# Ventilation.net
KiCad netlist of a schematic drawn in EAGLE
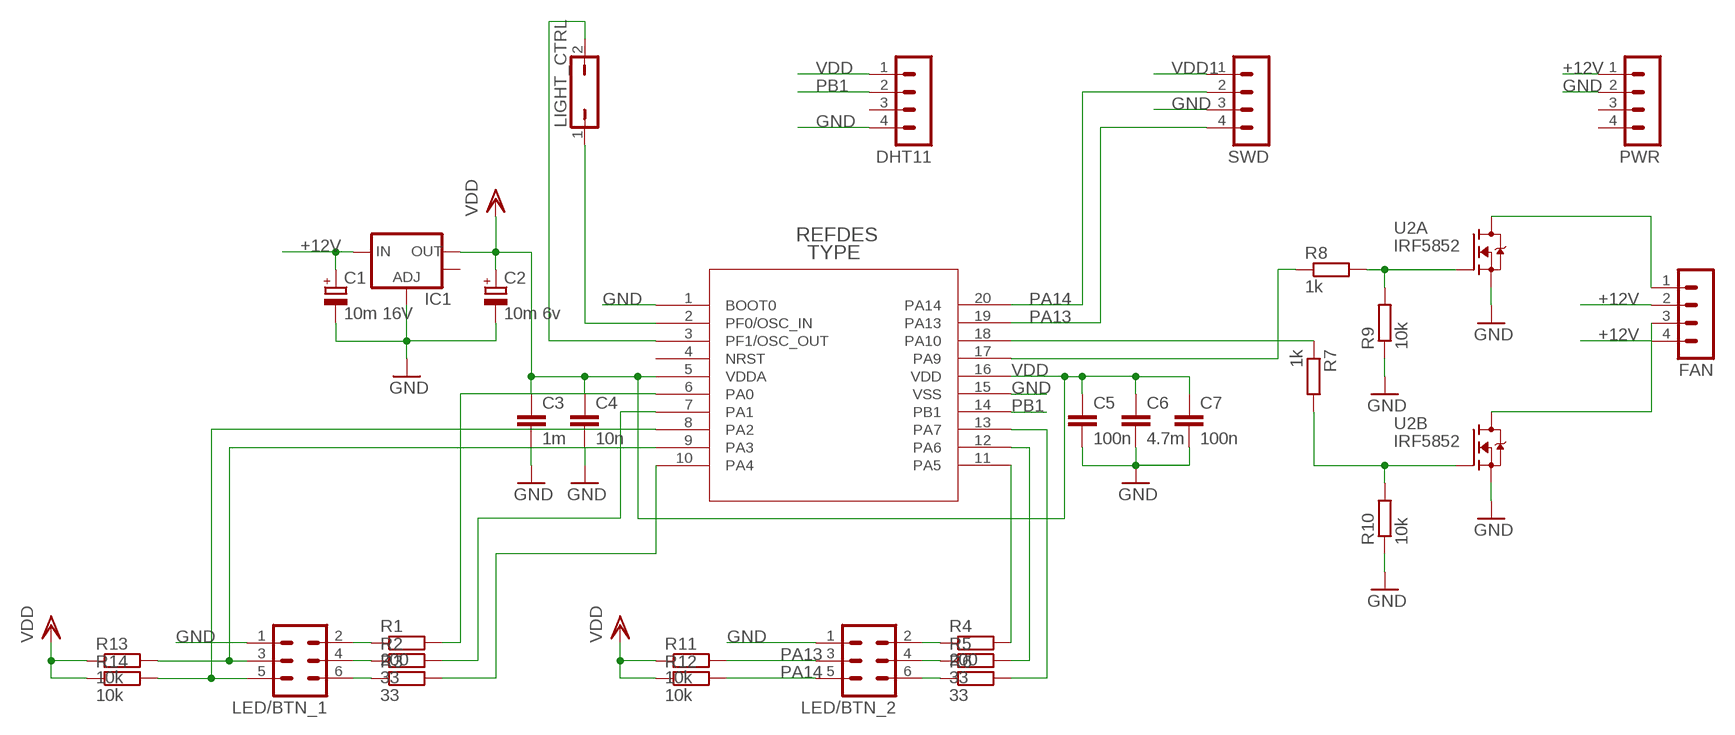
[diagram p0: schematic, sheet 1]

(export (version "E")
  (design (tool "Eeschema 10.0.6"))
  (components
    (comp (ref "C1")
      (value "10m 16V")
      (footprint "eagle-import:SMC_A")
      (libsource (lib "eagle-import") (part "CPOL-EUSMCA"))
    )
    (comp (ref "C2")
      (value "10m 6v")
      (footprint "eagle-import:SMC_A")
      (libsource (lib "eagle-import") (part "CPOL-EUSMCA"))
    )
    (comp (ref "C3")
      (value "1m")
      (footprint "eagle-import:C1206")
      (libsource (lib "eagle-import") (part "C-EUC1206"))
    )
    (comp (ref "C4")
      (value "10n")
      (footprint "eagle-import:C1206")
      (libsource (lib "eagle-import") (part "C-EUC1206"))
    )
    (comp (ref "C5")
      (value "100n")
      (footprint "eagle-import:C1206")
      (libsource (lib "eagle-import") (part "C-EUC1206"))
    )
    (comp (ref "C6")
      (value "4.7m")
      (footprint "eagle-import:C1206")
      (libsource (lib "eagle-import") (part "C-EUC1206"))
    )
    (comp (ref "C7")
      (value "100n")
      (footprint "eagle-import:C1206")
      (libsource (lib "eagle-import") (part "C-EUC1206"))
    )
    (comp (ref "DHT11")
      (value "MA04-1")
      (footprint "eagle-import:MA04-1")
      (libsource (lib "eagle-import") (part "MA04-1"))
    )
    (comp (ref "FAN")
      (value "MA04-1")
      (footprint "eagle-import:MA04-1")
      (libsource (lib "eagle-import") (part "MA04-1"))
    )
    (comp (ref "IC1")
      (value "V_REG_LM1117SOT223")
      (footprint "eagle-import:SOT223")
      (libsource (lib "eagle-import") (part "V_REG_LM1117SOT223"))
    )
    (comp (ref "LED/BTN_1")
      (value "MA03-2")
      (footprint "eagle-import:MA03-2")
      (libsource (lib "eagle-import") (part "MA03-2"))
    )
    (comp (ref "LED/BTN_2")
      (value "MA03-2")
      (footprint "eagle-import:MA03-2")
      (libsource (lib "eagle-import") (part "MA03-2"))
    )
    (comp (ref "LIGHT_CTRL")
      (value "JP1Q")
      (footprint "eagle-import:JP1")
      (libsource (lib "eagle-import") (part "JP1Q"))
    )
    (comp (ref "PWR")
      (value "MA04-1")
      (footprint "eagle-import:MA04-1")
      (libsource (lib "eagle-import") (part "MA04-1"))
    )
    (comp (ref "R1")
      (value "200")
      (footprint "eagle-import:R1206")
      (libsource (lib "eagle-import") (part "R-EU_R1206"))
    )
    (comp (ref "R2")
      (value "33")
      (footprint "eagle-import:R1206")
      (libsource (lib "eagle-import") (part "R-EU_R1206"))
    )
    (comp (ref "R3")
      (value "33")
      (footprint "eagle-import:R1206")
      (libsource (lib "eagle-import") (part "R-EU_R1206"))
    )
    (comp (ref "R4")
      (value "200")
      (footprint "eagle-import:R1206")
      (libsource (lib "eagle-import") (part "R-EU_R1206"))
    )
    (comp (ref "R5")
      (value "33")
      (footprint "eagle-import:R1206")
      (libsource (lib "eagle-import") (part "R-EU_R1206"))
    )
    (comp (ref "R6")
      (value "33")
      (footprint "eagle-import:R1206")
      (libsource (lib "eagle-import") (part "R-EU_R1206"))
    )
    (comp (ref "R7")
      (value "1k")
      (footprint "eagle-import:R1206")
      (libsource (lib "eagle-import") (part "R-EU_R1206"))
    )
    (comp (ref "R8")
      (value "1k")
      (footprint "eagle-import:R1206")
      (libsource (lib "eagle-import") (part "R-EU_R1206"))
    )
    (comp (ref "R9")
      (value "10k")
      (footprint "eagle-import:R1206")
      (libsource (lib "eagle-import") (part "R-EU_R1206"))
    )
    (comp (ref "R10")
      (value "10k")
      (footprint "eagle-import:R1206")
      (libsource (lib "eagle-import") (part "R-EU_R1206"))
    )
    (comp (ref "R11")
      (value "10k")
      (footprint "eagle-import:R1206")
      (libsource (lib "eagle-import") (part "R-EU_R1206"))
    )
    (comp (ref "R12")
      (value "10k")
      (footprint "eagle-import:R1206")
      (libsource (lib "eagle-import") (part "R-EU_R1206"))
    )
    (comp (ref "R13")
      (value "10k")
      (footprint "eagle-import:R1206")
      (libsource (lib "eagle-import") (part "R-EU_R1206"))
    )
    (comp (ref "R14")
      (value "10k")
      (footprint "eagle-import:R1206")
      (libsource (lib "eagle-import") (part "R-EU_R1206"))
    )
    (comp (ref "SWD")
      (value "MA04-1")
      (footprint "eagle-import:MA04-1")
      (libsource (lib "eagle-import") (part "MA04-1"))
    )
    (comp (ref "U$1")
      (value "STM32F050F4P6")
      (footprint "eagle-import:TSSOP20")
      (libsource (lib "eagle-import") (part "STM32F050F4P6"))
    )
    (comp (ref "U2")
      (value "IRF5852")
      (footprint "eagle-import:SOT23-6")
      (libsource (lib "eagle-import") (part "IRF5852"))
    )
  )
  (nets
    (net (code "1") (name "/+12V") (class "Default")
      (node (ref "C1") (pin "+") (pinfunction "+_+") (pintype "passive"))
      (node (ref "FAN") (pin "2") (pinfunction "2_2") (pintype "passive"))
      (node (ref "FAN") (pin "4") (pinfunction "4_4") (pintype "passive"))
      (node (ref "IC1") (pin "3") (pinfunction "IN_3") (pintype "input"))
      (node (ref "PWR") (pin "1") (pinfunction "1_1") (pintype "passive"))
    )
    (net (code "2") (name "/PA13") (class "Default")
      (node (ref "LED/BTN_2") (pin "3") (pinfunction "3_3") (pintype "passive"))
      (node (ref "R11") (pin "2") (pinfunction "2_2") (pintype "passive"))
      (node (ref "SWD") (pin "4") (pinfunction "4_4") (pintype "passive"))
      (node (ref "U$1") (pin "19") (pinfunction "PA13_19") (pintype "passive"))
    )
    (net (code "3") (name "/PA14") (class "Default")
      (node (ref "LED/BTN_2") (pin "5") (pinfunction "5_5") (pintype "passive"))
      (node (ref "R12") (pin "2") (pinfunction "2_2") (pintype "passive"))
      (node (ref "SWD") (pin "2") (pinfunction "2_2") (pintype "passive"))
      (node (ref "U$1") (pin "20") (pinfunction "PA14_20") (pintype "passive"))
    )
    (net (code "4") (name "/PB1") (class "Default")
      (node (ref "DHT11") (pin "2") (pinfunction "2_2") (pintype "passive"))
      (node (ref "U$1") (pin "14") (pinfunction "PB1_14") (pintype "passive"))
    )
    (net (code "5") (name "/VDD1") (class "Default")
      (node (ref "SWD") (pin "1") (pinfunction "1_1") (pintype "passive"))
    )
    (net (code "6") (name "GND") (class "Default")
      (node (ref "C1") (pin "-") (pinfunction "-_-") (pintype "passive"))
      (node (ref "C2") (pin "-") (pinfunction "-_-") (pintype "passive"))
      (node (ref "C3") (pin "2") (pinfunction "2_2") (pintype "passive"))
      (node (ref "C4") (pin "2") (pinfunction "2_2") (pintype "passive"))
      (node (ref "C5") (pin "2") (pinfunction "2_2") (pintype "passive"))
      (node (ref "C6") (pin "2") (pinfunction "2_2") (pintype "passive"))
      (node (ref "C7") (pin "2") (pinfunction "2_2") (pintype "passive"))
      (node (ref "DHT11") (pin "4") (pinfunction "4_4") (pintype "passive"))
      (node (ref "IC1") (pin "1") (pinfunction "ADJ_1") (pintype "input"))
      (node (ref "LED/BTN_1") (pin "1") (pinfunction "1_1") (pintype "passive"))
      (node (ref "LED/BTN_2") (pin "1") (pinfunction "1_1") (pintype "passive"))
      (node (ref "PWR") (pin "2") (pinfunction "2_2") (pintype "passive"))
      (node (ref "R10") (pin "1") (pinfunction "1_1") (pintype "passive"))
      (node (ref "R9") (pin "1") (pinfunction "1_1") (pintype "passive"))
      (node (ref "SWD") (pin "3") (pinfunction "3_3") (pintype "passive"))
      (node (ref "U$1") (pin "1") (pinfunction "BOOT0_1") (pintype "passive"))
      (node (ref "U$1") (pin "15") (pinfunction "VSS_15") (pintype "passive"))
      (node (ref "U2") (pin "2") (pinfunction "S_2") (pintype "passive"))
      (node (ref "U2") (pin "5") (pinfunction "S_5") (pintype "passive"))
    )
    (net (code "7") (name "Net-(LED/BTN_1-Pad2)") (class "Default")
      (node (ref "LED/BTN_1") (pin "2") (pinfunction "2_2") (pintype "passive"))
      (node (ref "R1") (pin "1") (pinfunction "1_1") (pintype "passive"))
    )
    (net (code "8") (name "Net-(LED/BTN_1-Pad4)") (class "Default")
      (node (ref "LED/BTN_1") (pin "4") (pinfunction "4_4") (pintype "passive"))
      (node (ref "R2") (pin "1") (pinfunction "1_1") (pintype "passive"))
    )
    (net (code "9") (name "Net-(LED/BTN_1-Pad6)") (class "Default")
      (node (ref "LED/BTN_1") (pin "6") (pinfunction "6_6") (pintype "passive"))
      (node (ref "R3") (pin "1") (pinfunction "1_1") (pintype "passive"))
    )
    (net (code "10") (name "Net-(LED/BTN_2-Pad2)") (class "Default")
      (node (ref "LED/BTN_2") (pin "2") (pinfunction "2_2") (pintype "passive"))
      (node (ref "R4") (pin "1") (pinfunction "1_1") (pintype "passive"))
    )
    (net (code "11") (name "Net-(LED/BTN_2-Pad4)") (class "Default")
      (node (ref "LED/BTN_2") (pin "4") (pinfunction "4_4") (pintype "passive"))
      (node (ref "R5") (pin "1") (pinfunction "1_1") (pintype "passive"))
    )
    (net (code "12") (name "Net-(LED/BTN_2-Pad6)") (class "Default")
      (node (ref "LED/BTN_2") (pin "6") (pinfunction "6_6") (pintype "passive"))
      (node (ref "R6") (pin "1") (pinfunction "1_1") (pintype "passive"))
    )
    (net (code "13") (name "Net-(U$1-PA0)") (class "Default")
      (node (ref "R1") (pin "2") (pinfunction "2_2") (pintype "passive"))
      (node (ref "U$1") (pin "6") (pinfunction "PA0_6") (pintype "passive"))
    )
    (net (code "14") (name "Net-(U$1-PA1)") (class "Default")
      (node (ref "R2") (pin "2") (pinfunction "2_2") (pintype "passive"))
      (node (ref "U$1") (pin "7") (pinfunction "PA1_7") (pintype "passive"))
    )
    (net (code "15") (name "Net-(U$1-PA2)") (class "Default")
      (node (ref "LED/BTN_1") (pin "5") (pinfunction "5_5") (pintype "passive"))
      (node (ref "R14") (pin "2") (pinfunction "2_2") (pintype "passive"))
      (node (ref "U$1") (pin "8") (pinfunction "PA2_8") (pintype "passive"))
    )
    (net (code "16") (name "Net-(U$1-PA3)") (class "Default")
      (node (ref "LED/BTN_1") (pin "3") (pinfunction "3_3") (pintype "passive"))
      (node (ref "R13") (pin "2") (pinfunction "2_2") (pintype "passive"))
      (node (ref "U$1") (pin "9") (pinfunction "PA3_9") (pintype "passive"))
    )
    (net (code "17") (name "Net-(U$1-PA4)") (class "Default")
      (node (ref "R3") (pin "2") (pinfunction "2_2") (pintype "passive"))
      (node (ref "U$1") (pin "10") (pinfunction "PA4_10") (pintype "passive"))
    )
    (net (code "18") (name "Net-(U$1-PA5)") (class "Default")
      (node (ref "R4") (pin "2") (pinfunction "2_2") (pintype "passive"))
      (node (ref "U$1") (pin "11") (pinfunction "PA5_11") (pintype "passive"))
    )
    (net (code "19") (name "Net-(U$1-PA6)") (class "Default")
      (node (ref "R5") (pin "2") (pinfunction "2_2") (pintype "passive"))
      (node (ref "U$1") (pin "12") (pinfunction "PA6_12") (pintype "passive"))
    )
    (net (code "20") (name "Net-(U$1-PA7)") (class "Default")
      (node (ref "R6") (pin "2") (pinfunction "2_2") (pintype "passive"))
      (node (ref "U$1") (pin "13") (pinfunction "PA7_13") (pintype "passive"))
    )
    (net (code "21") (name "Net-(U$1-PA9)") (class "Default")
      (node (ref "R8") (pin "1") (pinfunction "1_1") (pintype "passive"))
      (node (ref "U$1") (pin "17") (pinfunction "PA9_17") (pintype "passive"))
    )
    (net (code "22") (name "Net-(U$1-PA10)") (class "Default")
      (node (ref "R7") (pin "1") (pinfunction "1_1") (pintype "passive"))
      (node (ref "U$1") (pin "18") (pinfunction "PA10_18") (pintype "passive"))
    )
    (net (code "23") (name "Net-(U$1-PF0{slash}OSC_IN)") (class "Default")
      (node (ref "LIGHT_CTRL") (pin "1") (pinfunction "1_1") (pintype "passive"))
      (node (ref "U$1") (pin "2") (pinfunction "PF0/OSC_IN_2") (pintype "passive"))
    )
    (net (code "24") (name "Net-(U$1-PF1{slash}OSC_OUT)") (class "Default")
      (node (ref "LIGHT_CTRL") (pin "2") (pinfunction "2_2") (pintype "passive"))
      (node (ref "U$1") (pin "3") (pinfunction "PF1/OSC_OUT_3") (pintype "passive"))
    )
    (net (code "25") (name "Net-(U2A-D)") (class "Default")
      (node (ref "FAN") (pin "1") (pinfunction "1_1") (pintype "passive"))
      (node (ref "U2") (pin "6") (pinfunction "D_6") (pintype "passive"))
    )
    (net (code "26") (name "Net-(U2A-G)") (class "Default")
      (node (ref "R8") (pin "2") (pinfunction "2_2") (pintype "passive"))
      (node (ref "R9") (pin "2") (pinfunction "2_2") (pintype "passive"))
      (node (ref "U2") (pin "1") (pinfunction "G_1") (pintype "passive"))
    )
    (net (code "27") (name "Net-(U2B-D)") (class "Default")
      (node (ref "FAN") (pin "3") (pinfunction "3_3") (pintype "passive"))
      (node (ref "U2") (pin "4") (pinfunction "D_4") (pintype "passive"))
    )
    (net (code "28") (name "Net-(U2B-G)") (class "Default")
      (node (ref "R10") (pin "2") (pinfunction "2_2") (pintype "passive"))
      (node (ref "R7") (pin "2") (pinfunction "2_2") (pintype "passive"))
      (node (ref "U2") (pin "3") (pinfunction "G_3") (pintype "passive"))
    )
    (net (code "29") (name "VDD") (class "Default")
      (node (ref "C2") (pin "+") (pinfunction "+_+") (pintype "passive"))
      (node (ref "C3") (pin "1") (pinfunction "1_1") (pintype "passive"))
      (node (ref "C4") (pin "1") (pinfunction "1_1") (pintype "passive"))
      (node (ref "C5") (pin "1") (pinfunction "1_1") (pintype "passive"))
      (node (ref "C6") (pin "1") (pinfunction "1_1") (pintype "passive"))
      (node (ref "C7") (pin "1") (pinfunction "1_1") (pintype "passive"))
      (node (ref "DHT11") (pin "1") (pinfunction "1_1") (pintype "passive"))
      (node (ref "IC1") (pin "2") (pinfunction "OUT_2") (pintype "output"))
      (node (ref "R11") (pin "1") (pinfunction "1_1") (pintype "passive"))
      (node (ref "R12") (pin "1") (pinfunction "1_1") (pintype "passive"))
      (node (ref "R13") (pin "1") (pinfunction "1_1") (pintype "passive"))
      (node (ref "R14") (pin "1") (pinfunction "1_1") (pintype "passive"))
      (node (ref "U$1") (pin "16") (pinfunction "VDD_16") (pintype "passive"))
      (node (ref "U$1") (pin "5") (pinfunction "VDDA_5") (pintype "passive"))
    )
    (net (code "30") (name "unconnected-(DHT11-Pad3)") (class "Default")
      (node (ref "DHT11") (pin "3") (pinfunction "3_3") (pintype "passive"))
    )
    (net (code "31") (name "unconnected-(IC1-OUT-Pad4)") (class "Default")
      (node (ref "IC1") (pin "4") (pinfunction "OUT_4") (pintype "output"))
    )
    (net (code "32") (name "unconnected-(PWR-Pad3)") (class "Default")
      (node (ref "PWR") (pin "3") (pinfunction "3_3") (pintype "passive"))
    )
    (net (code "33") (name "unconnected-(PWR-Pad4)") (class "Default")
      (node (ref "PWR") (pin "4") (pinfunction "4_4") (pintype "passive"))
    )
    (net (code "34") (name "unconnected-(U$1-NRST-Pad4)") (class "Default")
      (node (ref "U$1") (pin "4") (pinfunction "NRST_4") (pintype "passive"))
    )
  )
)
